# power-icl7662.net
KiCad netlist of a schematic drawn in EAGLE
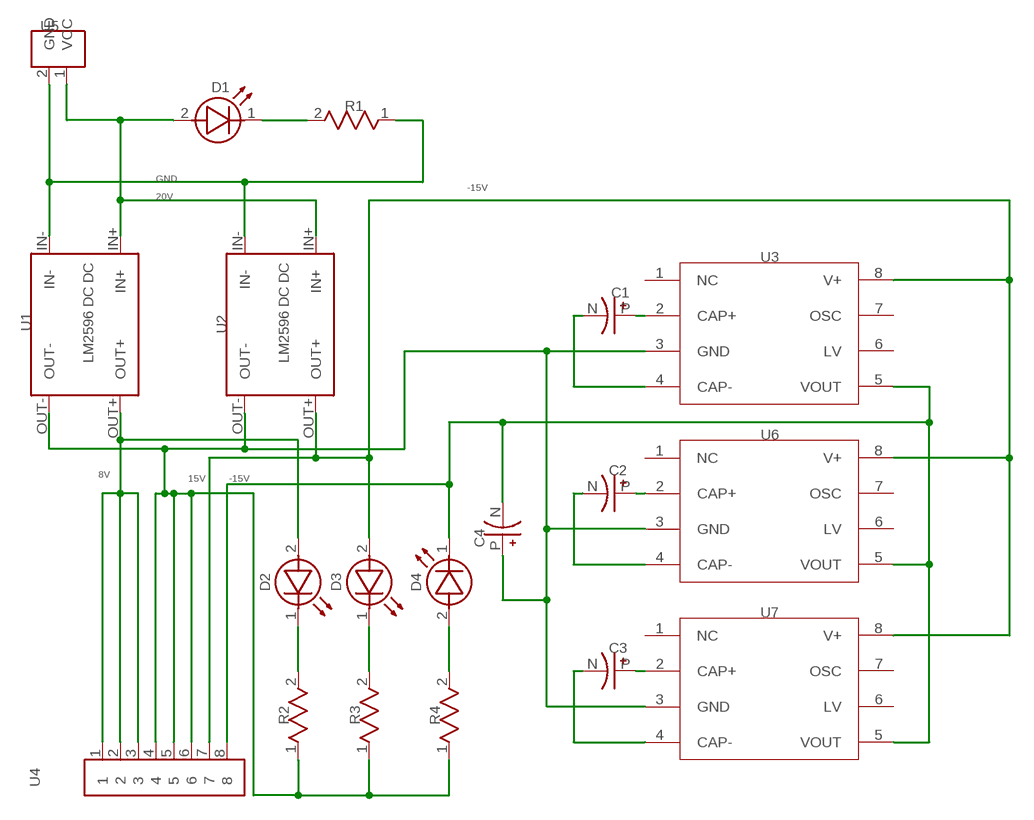
[diagram p0: schematic, sheet 1]

(export (version "E")
  (design (tool "Eeschema 10.0.6"))
  (components
    (comp (ref "C1")
      (value "10µF 25V")
      (footprint "eagle-import:CAPPRD250W50D500H1100")
      (libsource (lib "eagle-import") (part "EEUHD1H100"))
    )
    (comp (ref "C2")
      (value "10µF 25V")
      (footprint "eagle-import:CAPPRD250W50D500H1100")
      (libsource (lib "eagle-import") (part "EEUHD1H100"))
    )
    (comp (ref "C3")
      (value "10 µF 25V")
      (footprint "eagle-import:CAPPRD250W50D500H1100")
      (libsource (lib "eagle-import") (part "EEUHD1H100"))
    )
    (comp (ref "C4")
      (value "47µF 25V")
      (footprint "eagle-import:CAPPRD250W50D500H1100")
      (libsource (lib "eagle-import") (part "EEUHD1H100"))
    )
    (comp (ref "D1")
      (value "RED")
      (footprint "eagle-import:LED100")
      (libsource (lib "eagle-import") (part "LED"))
    )
    (comp (ref "D2")
      (value "GREEN")
      (footprint "eagle-import:LED100")
      (libsource (lib "eagle-import") (part "LED"))
    )
    (comp (ref "D3")
      (value "YELLOW")
      (footprint "eagle-import:LED100")
      (libsource (lib "eagle-import") (part "LED"))
    )
    (comp (ref "D4")
      (value "BLEUE")
      (footprint "eagle-import:LED100")
      (libsource (lib "eagle-import") (part "LED"))
    )
    (comp (ref "R1")
      (value "2200")
      (footprint "eagle-import:RESAD1190W58L750D250")
      (fields (field (name "MANUFACTURER") "Vishay"))
      (libsource (lib "eagle-import") (part "SFR2500001002FR500"))
    )
    (comp (ref "R2")
      (value "2200")
      (footprint "eagle-import:RESAD1190W58L750D250")
      (fields (field (name "MANUFACTURER") "Vishay"))
      (libsource (lib "eagle-import") (part "SFR2500001002FR500"))
    )
    (comp (ref "R3")
      (value "2200")
      (footprint "eagle-import:RESAD1190W58L750D250")
      (fields (field (name "MANUFACTURER") "Vishay"))
      (libsource (lib "eagle-import") (part "SFR2500001002FR500"))
    )
    (comp (ref "R4")
      (value "2200")
      (footprint "eagle-import:RESAD1190W58L750D250")
      (fields (field (name "MANUFACTURER") "Vishay"))
      (libsource (lib "eagle-import") (part "SFR2500001002FR500"))
    )
    (comp (ref "U1")
      (value "LM2596DCDC")
      (footprint "eagle-import:LM2596DCDC")
      (libsource (lib "eagle-import") (part "LM2596DCDC"))
    )
    (comp (ref "U2")
      (value "LM2596DCDC")
      (footprint "eagle-import:LM2596DCDC")
      (libsource (lib "eagle-import") (part "LM2596DCDC"))
    )
    (comp (ref "U3")
      (value "ICL7662-PDIP")
      (footprint "eagle-import:DIL-08")
      (libsource (lib "eagle-import") (part "ICL7662-PDIP"))
    )
    (comp (ref "U4")
      (value "1X8.PTS")
      (footprint "eagle-import:PHOENIX-200-8")
      (libsource (lib "eagle-import") (part "1X8.PTS"))
    )
    (comp (ref "U5")
      (value "1X2.PTS")
      (footprint "eagle-import:PHOENIX-200-2")
      (libsource (lib "eagle-import") (part "1X2.PTS"))
    )
    (comp (ref "U6")
      (value "ICL7662-PDIP")
      (footprint "eagle-import:DIL-08")
      (libsource (lib "eagle-import") (part "ICL7662-PDIP"))
    )
    (comp (ref "U7")
      (value "ICL7662-PDIP")
      (footprint "eagle-import:DIL-08")
      (libsource (lib "eagle-import") (part "ICL7662-PDIP"))
    )
  )
  (nets
    (net (code "1") (name "/GND") (class "Default")
      (node (ref "C4") (pin "P") (pinfunction "P_P") (pintype "passive"))
      (node (ref "R1") (pin "1") (pinfunction "1_1") (pintype "passive"))
      (node (ref "R2") (pin "1") (pinfunction "1_1") (pintype "passive"))
      (node (ref "R3") (pin "1") (pinfunction "1_1") (pintype "passive"))
      (node (ref "R4") (pin "1") (pinfunction "1_1") (pintype "passive"))
      (node (ref "U1") (pin "IN-") (pinfunction "IN-_IN-") (pintype "power_in"))
      (node (ref "U1") (pin "OUT-") (pinfunction "OUT-_OUT-") (pintype "power_in"))
      (node (ref "U2") (pin "IN-") (pinfunction "IN-_IN-") (pintype "power_in"))
      (node (ref "U2") (pin "OUT-") (pinfunction "OUT-_OUT-") (pintype "power_in"))
      (node (ref "U3") (pin "3") (pinfunction "GND_3") (pintype "bidirectional"))
      (node (ref "U4") (pin "4") (pinfunction "4_4") (pintype "power_in"))
      (node (ref "U4") (pin "5") (pinfunction "5_5") (pintype "power_in"))
      (node (ref "U4") (pin "6") (pinfunction "6_6") (pintype "power_in"))
      (node (ref "U5") (pin "2") (pinfunction "GND_2") (pintype "power_in"))
      (node (ref "U6") (pin "3") (pinfunction "GND_3") (pintype "bidirectional"))
      (node (ref "U7") (pin "3") (pinfunction "GND_3") (pintype "bidirectional"))
    )
    (net (code "2") (name "Net-(D1-A)") (class "Default")
      (node (ref "D1") (pin "2") (pinfunction "A_2") (pintype "passive"))
      (node (ref "U1") (pin "IN+") (pinfunction "IN+_IN+") (pintype "power_in"))
      (node (ref "U2") (pin "IN+") (pinfunction "IN+_IN+") (pintype "power_in"))
      (node (ref "U5") (pin "1") (pinfunction "VCC_1") (pintype "power_in"))
    )
    (net (code "3") (name "Net-(D1-K)") (class "Default")
      (node (ref "D1") (pin "1") (pinfunction "K_1") (pintype "passive"))
      (node (ref "R1") (pin "2") (pinfunction "2_2") (pintype "passive"))
    )
    (net (code "4") (name "Net-(D2-A)") (class "Default")
      (node (ref "D2") (pin "2") (pinfunction "A_2") (pintype "passive"))
      (node (ref "U1") (pin "OUT+") (pinfunction "OUT+_OUT+") (pintype "power_in"))
      (node (ref "U4") (pin "1") (pinfunction "1_1") (pintype "power_in"))
      (node (ref "U4") (pin "2") (pinfunction "2_2") (pintype "power_in"))
      (node (ref "U4") (pin "3") (pinfunction "3_3") (pintype "power_in"))
    )
    (net (code "5") (name "Net-(D2-K)") (class "Default")
      (node (ref "D2") (pin "1") (pinfunction "K_1") (pintype "passive"))
      (node (ref "R2") (pin "2") (pinfunction "2_2") (pintype "passive"))
    )
    (net (code "6") (name "Net-(D3-A)") (class "Default")
      (node (ref "D3") (pin "2") (pinfunction "A_2") (pintype "passive"))
      (node (ref "U2") (pin "OUT+") (pinfunction "OUT+_OUT+") (pintype "power_in"))
      (node (ref "U3") (pin "8") (pinfunction "V+_8") (pintype "bidirectional"))
      (node (ref "U4") (pin "7") (pinfunction "7_7") (pintype "power_in"))
      (node (ref "U6") (pin "8") (pinfunction "V+_8") (pintype "bidirectional"))
      (node (ref "U7") (pin "8") (pinfunction "V+_8") (pintype "bidirectional"))
    )
    (net (code "7") (name "Net-(D3-K)") (class "Default")
      (node (ref "D3") (pin "1") (pinfunction "K_1") (pintype "passive"))
      (node (ref "R3") (pin "2") (pinfunction "2_2") (pintype "passive"))
    )
    (net (code "8") (name "Net-(D4-A)") (class "Default")
      (node (ref "D4") (pin "2") (pinfunction "A_2") (pintype "passive"))
      (node (ref "R4") (pin "2") (pinfunction "2_2") (pintype "passive"))
    )
    (net (code "9") (name "Net-(D4-K)") (class "Default")
      (node (ref "C4") (pin "N") (pinfunction "N_N") (pintype "passive"))
      (node (ref "D4") (pin "1") (pinfunction "K_1") (pintype "passive"))
      (node (ref "U3") (pin "5") (pinfunction "VOUT_5") (pintype "bidirectional"))
      (node (ref "U4") (pin "8") (pinfunction "8_8") (pintype "power_in"))
      (node (ref "U6") (pin "5") (pinfunction "VOUT_5") (pintype "bidirectional"))
      (node (ref "U7") (pin "5") (pinfunction "VOUT_5") (pintype "bidirectional"))
    )
    (net (code "10") (name "Net-(U3-CAP+)") (class "Default")
      (node (ref "C1") (pin "P") (pinfunction "P_P") (pintype "passive"))
      (node (ref "U3") (pin "2") (pinfunction "CAP+_2") (pintype "bidirectional"))
    )
    (net (code "11") (name "Net-(U3-CAP-)") (class "Default")
      (node (ref "C1") (pin "N") (pinfunction "N_N") (pintype "passive"))
      (node (ref "U3") (pin "4") (pinfunction "CAP-_4") (pintype "bidirectional"))
    )
    (net (code "12") (name "Net-(U6-CAP+)") (class "Default")
      (node (ref "C2") (pin "P") (pinfunction "P_P") (pintype "passive"))
      (node (ref "U6") (pin "2") (pinfunction "CAP+_2") (pintype "bidirectional"))
    )
    (net (code "13") (name "Net-(U6-CAP-)") (class "Default")
      (node (ref "C2") (pin "N") (pinfunction "N_N") (pintype "passive"))
      (node (ref "U6") (pin "4") (pinfunction "CAP-_4") (pintype "bidirectional"))
    )
    (net (code "14") (name "Net-(U7-CAP+)") (class "Default")
      (node (ref "C3") (pin "P") (pinfunction "P_P") (pintype "passive"))
      (node (ref "U7") (pin "2") (pinfunction "CAP+_2") (pintype "bidirectional"))
    )
    (net (code "15") (name "Net-(U7-CAP-)") (class "Default")
      (node (ref "C3") (pin "N") (pinfunction "N_N") (pintype "passive"))
      (node (ref "U7") (pin "4") (pinfunction "CAP-_4") (pintype "bidirectional"))
    )
    (net (code "16") (name "unconnected-(U3-LV-Pad6)") (class "Default")
      (node (ref "U3") (pin "6") (pinfunction "LV_6") (pintype "bidirectional"))
    )
    (net (code "17") (name "unconnected-(U3-NC-Pad1)") (class "Default")
      (node (ref "U3") (pin "1") (pinfunction "NC_1") (pintype "bidirectional"))
    )
    (net (code "18") (name "unconnected-(U3-OSC-Pad7)") (class "Default")
      (node (ref "U3") (pin "7") (pinfunction "OSC_7") (pintype "bidirectional"))
    )
    (net (code "19") (name "unconnected-(U6-LV-Pad6)") (class "Default")
      (node (ref "U6") (pin "6") (pinfunction "LV_6") (pintype "bidirectional"))
    )
    (net (code "20") (name "unconnected-(U6-NC-Pad1)") (class "Default")
      (node (ref "U6") (pin "1") (pinfunction "NC_1") (pintype "bidirectional"))
    )
    (net (code "21") (name "unconnected-(U6-OSC-Pad7)") (class "Default")
      (node (ref "U6") (pin "7") (pinfunction "OSC_7") (pintype "bidirectional"))
    )
    (net (code "22") (name "unconnected-(U7-LV-Pad6)") (class "Default")
      (node (ref "U7") (pin "6") (pinfunction "LV_6") (pintype "bidirectional"))
    )
    (net (code "23") (name "unconnected-(U7-NC-Pad1)") (class "Default")
      (node (ref "U7") (pin "1") (pinfunction "NC_1") (pintype "bidirectional"))
    )
    (net (code "24") (name "unconnected-(U7-OSC-Pad7)") (class "Default")
      (node (ref "U7") (pin "7") (pinfunction "OSC_7") (pintype "bidirectional"))
    )
  )
)
